# octanis_eps_v03.net
KiCad netlist of a schematic drawn in EAGLE
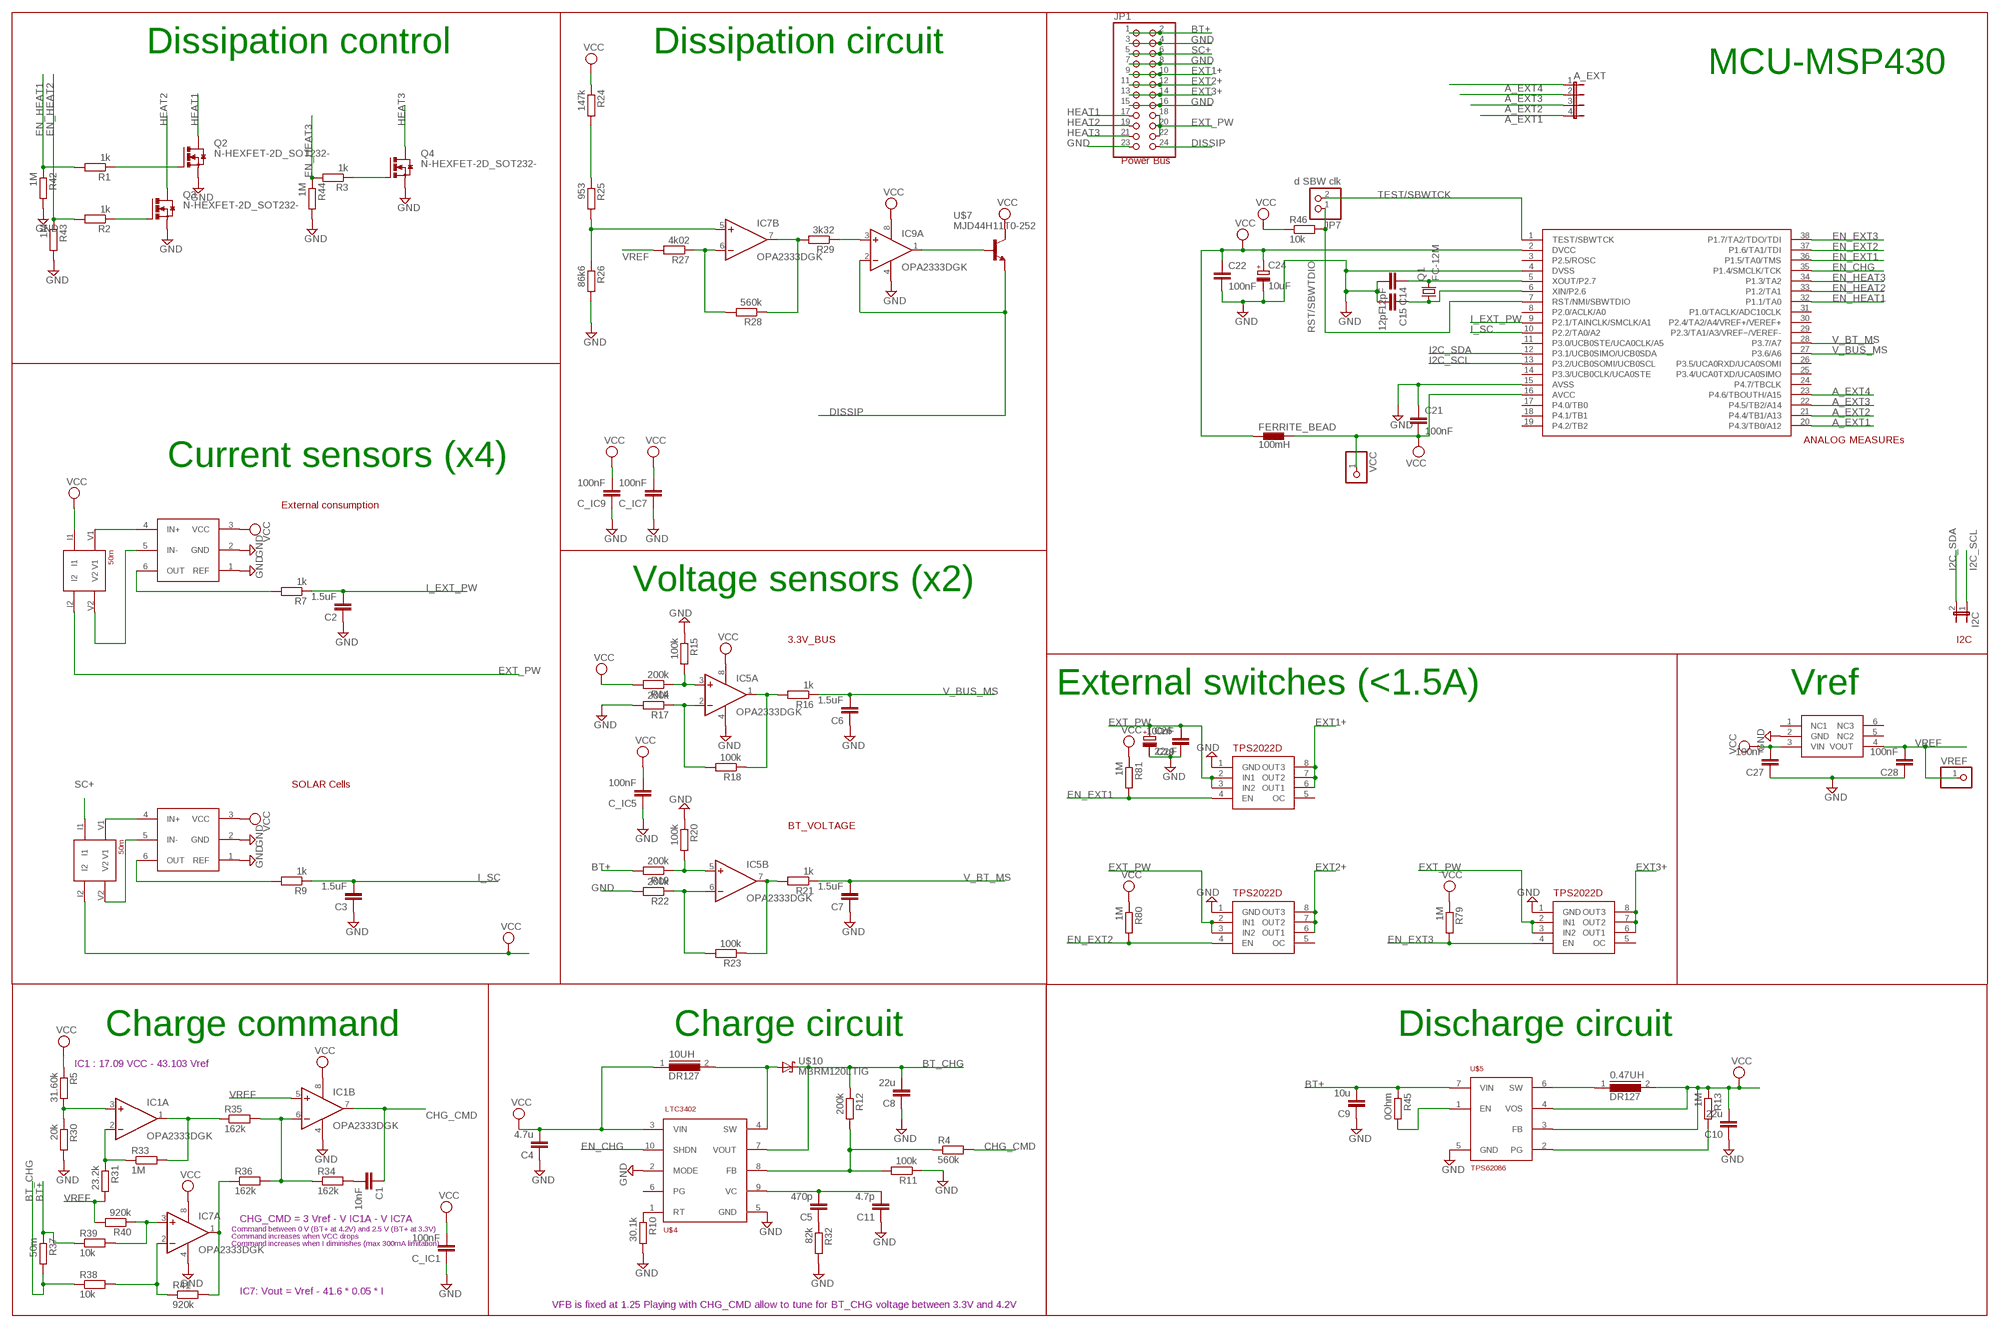
[diagram p0: schematic, sheet 1]

(export (version "E")
  (design (tool "Eeschema 10.0.6"))
  (components
    (comp (ref "0.47UH")
      (value "DR127")
      (footprint "eagle-import:DR127")
      (libsource (lib "eagle-import") (part "DR127"))
    )
    (comp (ref "10UH")
      (value "DR127")
      (footprint "eagle-import:DR127")
      (libsource (lib "eagle-import") (part "DR127"))
    )
    (comp (ref "A_EXT")
      (value "JP4E")
      (footprint "eagle-import:JP4")
      (libsource (lib "eagle-import") (part "JP4E"))
    )
    (comp (ref "C1")
      (value "10nF")
      (footprint "eagle-import:C0603")
      (libsource (lib "eagle-import") (part "C-EUC0603"))
    )
    (comp (ref "C2")
      (value "1.5uF")
      (footprint "eagle-import:C0603")
      (libsource (lib "eagle-import") (part "C-EUC0603"))
    )
    (comp (ref "C3")
      (value "1.5uF")
      (footprint "eagle-import:C0603")
      (libsource (lib "eagle-import") (part "C-EUC0603"))
    )
    (comp (ref "C4")
      (value "4.7u")
      (footprint "eagle-import:C1206")
      (libsource (lib "eagle-import") (part "C-EUC1206"))
    )
    (comp (ref "C5")
      (value "470p")
      (footprint "eagle-import:C0603")
      (libsource (lib "eagle-import") (part "C-EUC0603"))
    )
    (comp (ref "C6")
      (value "1.5uF")
      (footprint "eagle-import:C0603")
      (libsource (lib "eagle-import") (part "C-EUC0603"))
    )
    (comp (ref "C7")
      (value "1.5uF")
      (footprint "eagle-import:C0603")
      (libsource (lib "eagle-import") (part "C-EUC0603"))
    )
    (comp (ref "C8")
      (value "22u")
      (footprint "eagle-import:C0603")
      (libsource (lib "eagle-import") (part "C-EUC0603"))
    )
    (comp (ref "C9")
      (value "10u")
      (footprint "eagle-import:C1206")
      (libsource (lib "eagle-import") (part "C-EUC1206"))
    )
    (comp (ref "C10")
      (value "22u")
      (footprint "eagle-import:C1206")
      (libsource (lib "eagle-import") (part "C-EUC1206"))
    )
    (comp (ref "C11")
      (value "4.7p")
      (footprint "eagle-import:C0603")
      (libsource (lib "eagle-import") (part "C-EUC0603"))
    )
    (comp (ref "C14")
      (value "12pF")
      (footprint "eagle-import:C0603")
      (libsource (lib "eagle-import") (part "C-EUC0603"))
    )
    (comp (ref "C15")
      (value "12pF")
      (footprint "eagle-import:C0603")
      (libsource (lib "eagle-import") (part "C-EUC0603"))
    )
    (comp (ref "C21")
      (value "100nF")
      (footprint "eagle-import:C0603")
      (libsource (lib "eagle-import") (part "C-EUC0603"))
    )
    (comp (ref "C22")
      (value "100nF")
      (footprint "eagle-import:C0603")
      (libsource (lib "eagle-import") (part "C-EUC0603"))
    )
    (comp (ref "C24")
      (value "10uF")
      (footprint "eagle-import:A_3216-18R")
      (libsource (lib "eagle-import") (part "CPOL-EUA/3216-18R"))
    )
    (comp (ref "C26")
      (value "22uF")
      (footprint "eagle-import:A_3216-18R")
      (libsource (lib "eagle-import") (part "CPOL-EUA/3216-18R"))
    )
    (comp (ref "C27")
      (value "100nF")
      (footprint "eagle-import:C0603")
      (libsource (lib "eagle-import") (part "C-EUC0603"))
    )
    (comp (ref "C28")
      (value "100nF")
      (footprint "eagle-import:C0603")
      (libsource (lib "eagle-import") (part "C-EUC0603"))
    )
    (comp (ref "C29")
      (value "100nF")
      (footprint "eagle-import:C0603")
      (libsource (lib "eagle-import") (part "C-EUC0603"))
    )
    (comp (ref "C_IC1")
      (value "100nF")
      (footprint "eagle-import:C0603")
      (libsource (lib "eagle-import") (part "C-EUC0603"))
    )
    (comp (ref "C_IC5")
      (value "100nF")
      (footprint "eagle-import:C0603")
      (libsource (lib "eagle-import") (part "C-EUC0603"))
    )
    (comp (ref "C_IC7")
      (value "100nF")
      (footprint "eagle-import:C0603")
      (libsource (lib "eagle-import") (part "C-EUC0603"))
    )
    (comp (ref "C_IC9")
      (value "100nF")
      (footprint "eagle-import:C0603")
      (libsource (lib "eagle-import") (part "C-EUC0603"))
    )
    (comp (ref "FERRITE_BEAD")
      (value "100mH")
      (footprint "eagle-import:0402")
      (libsource (lib "eagle-import") (part "BLM15HD601SN1"))
    )
    (comp (ref "I2C")
      (value "JP1E")
      (footprint "eagle-import:JP1")
      (libsource (lib "eagle-import") (part "JP1E"))
    )
    (comp (ref "IC1")
      (value "OPA2333DGK")
      (footprint "eagle-import:MSOP08")
      (libsource (lib "eagle-import") (part "OPA2333DGK"))
    )
    (comp (ref "IC5")
      (value "OPA2333DGK")
      (footprint "eagle-import:MSOP08")
      (libsource (lib "eagle-import") (part "OPA2333DGK"))
    )
    (comp (ref "IC7")
      (value "OPA2333DGK")
      (footprint "eagle-import:MSOP08")
      (libsource (lib "eagle-import") (part "OPA2333DGK"))
    )
    (comp (ref "IC9")
      (value "OPA2333DGK")
      (footprint "eagle-import:MSOP08")
      (libsource (lib "eagle-import") (part "OPA2333DGK"))
    )
    (comp (ref "JP1")
      (value "PINHD-2X12")
      (footprint "eagle-import:2X12")
      (libsource (lib "eagle-import") (part "PINHD-2X12"))
    )
    (comp (ref "JP7")
      (value "d SBW clk")
      (footprint "eagle-import:1X02")
      (libsource (lib "eagle-import") (part "PINHD-1X2"))
    )
    (comp (ref "Q1")
      (value "FC-12M")
      (footprint "eagle-import:FC-12M")
      (libsource (lib "eagle-import") (part "FC-12M"))
    )
    (comp (ref "Q2")
      (value "N-HEXFET-2D_SOT232-")
      (footprint "eagle-import:SOT223")
      (libsource (lib "eagle-import") (part "N-HEXFET-2D_?-SOT232"))
    )
    (comp (ref "Q3")
      (value "N-HEXFET-2D_SOT232-")
      (footprint "eagle-import:SOT223")
      (libsource (lib "eagle-import") (part "N-HEXFET-2D_?-SOT232"))
    )
    (comp (ref "Q4")
      (value "N-HEXFET-2D_SOT232-")
      (footprint "eagle-import:SOT223")
      (libsource (lib "eagle-import") (part "N-HEXFET-2D_?-SOT232"))
    )
    (comp (ref "R1")
      (value "1k")
      (footprint "eagle-import:R0603")
      (libsource (lib "eagle-import") (part "R-EU_R0603"))
    )
    (comp (ref "R2")
      (value "1k")
      (footprint "eagle-import:R0603")
      (libsource (lib "eagle-import") (part "R-EU_R0603"))
    )
    (comp (ref "R3")
      (value "1k")
      (footprint "eagle-import:R0603")
      (libsource (lib "eagle-import") (part "R-EU_R0603"))
    )
    (comp (ref "R4")
      (value "560k")
      (footprint "eagle-import:R0603")
      (libsource (lib "eagle-import") (part "R-EU_R0603"))
    )
    (comp (ref "R5")
      (value "31.60k")
      (footprint "eagle-import:R0603")
      (libsource (lib "eagle-import") (part "R-EU_R0603"))
    )
    (comp (ref "R7")
      (value "1k")
      (footprint "eagle-import:R0603")
      (libsource (lib "eagle-import") (part "R-EU_R0603"))
    )
    (comp (ref "R9")
      (value "1k")
      (footprint "eagle-import:R0603")
      (libsource (lib "eagle-import") (part "R-EU_R0603"))
    )
    (comp (ref "R10")
      (value "30.1k")
      (footprint "eagle-import:R0603")
      (libsource (lib "eagle-import") (part "R-EU_R0603"))
    )
    (comp (ref "R11")
      (value "100k")
      (footprint "eagle-import:R0603")
      (libsource (lib "eagle-import") (part "R-EU_R0603"))
    )
    (comp (ref "R12")
      (value "200k")
      (footprint "eagle-import:R0603")
      (libsource (lib "eagle-import") (part "R-EU_R0603"))
    )
    (comp (ref "R13")
      (value "1M")
      (footprint "eagle-import:R0603")
      (libsource (lib "eagle-import") (part "R-EU_R0603"))
    )
    (comp (ref "R14")
      (value "200k")
      (footprint "eagle-import:R0603")
      (libsource (lib "eagle-import") (part "R-EU_R0603"))
    )
    (comp (ref "R15")
      (value "100k")
      (footprint "eagle-import:R0603")
      (libsource (lib "eagle-import") (part "R-EU_R0603"))
    )
    (comp (ref "R16")
      (value "1k")
      (footprint "eagle-import:R0603")
      (libsource (lib "eagle-import") (part "R-EU_R0603"))
    )
    (comp (ref "R17")
      (value "200k")
      (footprint "eagle-import:R0603")
      (libsource (lib "eagle-import") (part "R-EU_R0603"))
    )
    (comp (ref "R18")
      (value "100k")
      (footprint "eagle-import:R0603")
      (libsource (lib "eagle-import") (part "R-EU_R0603"))
    )
    (comp (ref "R19")
      (value "200k")
      (footprint "eagle-import:R0603")
      (libsource (lib "eagle-import") (part "R-EU_R0603"))
    )
    (comp (ref "R20")
      (value "100k")
      (footprint "eagle-import:R0603")
      (libsource (lib "eagle-import") (part "R-EU_R0603"))
    )
    (comp (ref "R21")
      (value "1k")
      (footprint "eagle-import:R0603")
      (libsource (lib "eagle-import") (part "R-EU_R0603"))
    )
    (comp (ref "R22")
      (value "200k")
      (footprint "eagle-import:R0603")
      (libsource (lib "eagle-import") (part "R-EU_R0603"))
    )
    (comp (ref "R23")
      (value "100k")
      (footprint "eagle-import:R0603")
      (libsource (lib "eagle-import") (part "R-EU_R0603"))
    )
    (comp (ref "R24")
      (value "147k")
      (footprint "eagle-import:R0603")
      (libsource (lib "eagle-import") (part "R-EU_R0603"))
    )
    (comp (ref "R25")
      (value "953")
      (footprint "eagle-import:R0603")
      (libsource (lib "eagle-import") (part "R-EU_R0603"))
    )
    (comp (ref "R26")
      (value "86k6")
      (footprint "eagle-import:R0603")
      (libsource (lib "eagle-import") (part "R-EU_R0603"))
    )
    (comp (ref "R27")
      (value "4k02")
      (footprint "eagle-import:R0603")
      (libsource (lib "eagle-import") (part "R-EU_R0603"))
    )
    (comp (ref "R28")
      (value "560k")
      (footprint "eagle-import:R0603")
      (libsource (lib "eagle-import") (part "R-EU_R0603"))
    )
    (comp (ref "R29")
      (value "3k32")
      (footprint "eagle-import:R0603")
      (libsource (lib "eagle-import") (part "R-EU_R0603"))
    )
    (comp (ref "R30")
      (value "20k")
      (footprint "eagle-import:R0603")
      (libsource (lib "eagle-import") (part "R-EU_R0603"))
    )
    (comp (ref "R31")
      (value "23.2k")
      (footprint "eagle-import:R0603")
      (libsource (lib "eagle-import") (part "R-EU_R0603"))
    )
    (comp (ref "R32")
      (value "82k")
      (footprint "eagle-import:R0603")
      (libsource (lib "eagle-import") (part "R-EU_R0603"))
    )
    (comp (ref "R33")
      (value "1M")
      (footprint "eagle-import:R0603")
      (libsource (lib "eagle-import") (part "R-EU_R0603"))
    )
    (comp (ref "R34")
      (value "162k")
      (footprint "eagle-import:R0603")
      (libsource (lib "eagle-import") (part "R-EU_R0603"))
    )
    (comp (ref "R35")
      (value "162k")
      (footprint "eagle-import:R0603")
      (libsource (lib "eagle-import") (part "R-EU_R0603"))
    )
    (comp (ref "R36")
      (value "162k")
      (footprint "eagle-import:R0603")
      (libsource (lib "eagle-import") (part "R-EU_R0603"))
    )
    (comp (ref "R37")
      (value "50m")
      (footprint "eagle-import:R1206")
      (libsource (lib "eagle-import") (part "R-EU_R1206"))
    )
    (comp (ref "R38")
      (value "10k")
      (footprint "eagle-import:R0603")
      (libsource (lib "eagle-import") (part "R-EU_R0603"))
    )
    (comp (ref "R39")
      (value "10k")
      (footprint "eagle-import:R0603")
      (libsource (lib "eagle-import") (part "R-EU_R0603"))
    )
    (comp (ref "R40")
      (value "920k")
      (footprint "eagle-import:R0603")
      (libsource (lib "eagle-import") (part "R-EU_R0603"))
    )
    (comp (ref "R41")
      (value "920k")
      (footprint "eagle-import:R0603")
      (libsource (lib "eagle-import") (part "R-EU_R0603"))
    )
    (comp (ref "R42")
      (value "1M")
      (footprint "eagle-import:R0603")
      (libsource (lib "eagle-import") (part "R-EU_R0603"))
    )
    (comp (ref "R43")
      (value "1M")
      (footprint "eagle-import:R0603")
      (libsource (lib "eagle-import") (part "R-EU_R0603"))
    )
    (comp (ref "R44")
      (value "1M")
      (footprint "eagle-import:R0603")
      (libsource (lib "eagle-import") (part "R-EU_R0603"))
    )
    (comp (ref "R45")
      (value "0Ohm")
      (footprint "eagle-import:R0603")
      (libsource (lib "eagle-import") (part "R-EU_R0603"))
    )
    (comp (ref "R46")
      (value "10k")
      (footprint "eagle-import:R0603")
      (libsource (lib "eagle-import") (part "R-EU_R0603"))
    )
    (comp (ref "R79")
      (value "1M")
      (footprint "eagle-import:R0603")
      (libsource (lib "eagle-import") (part "R-EU_R0603"))
    )
    (comp (ref "R80")
      (value "1M")
      (footprint "eagle-import:R0603")
      (libsource (lib "eagle-import") (part "R-EU_R0603"))
    )
    (comp (ref "R81")
      (value "1M")
      (footprint "eagle-import:R0603")
      (libsource (lib "eagle-import") (part "R-EU_R0603"))
    )
    (comp (ref "U$1")
      (value "50m")
      (footprint "eagle-import:4PADS_RESISTOR")
      (libsource (lib "eagle-import") (part "CURRENT_RESISTOR"))
    )
    (comp (ref "U$2")
      (value "INA213")
      (footprint "eagle-import:SC70-6")
      (libsource (lib "eagle-import") (part "INA213"))
    )
    (comp (ref "U$3")
      (value "INA213")
      (footprint "eagle-import:SC70-6")
      (libsource (lib "eagle-import") (part "INA213"))
    )
    (comp (ref "U$4")
      (value "LTC3402")
      (footprint "eagle-import:MSOP10")
      (libsource (lib "eagle-import") (part "LTC3402"))
    )
    (comp (ref "U$5")
      (value "TPS62086")
      (footprint "eagle-import:QFN-7")
      (libsource (lib "eagle-import") (part "TPS62086"))
    )
    (comp (ref "U$6")
      (value "MSP430G2544")
      (footprint "eagle-import:TSSOP38_MSPGXX44_SERIES")
      (libsource (lib "eagle-import") (part "MSP430G2544"))
    )
    (comp (ref "U$7")
      (value "MJD44H11T0-252")
      (footprint "eagle-import:TO252")
      (libsource (lib "eagle-import") (part "MJD44H11T0-252"))
    )
    (comp (ref "U$8")
      (value "50m")
      (footprint "eagle-import:4PADS_RESISTOR")
      (libsource (lib "eagle-import") (part "CURRENT_RESISTOR"))
    )
    (comp (ref "U$10")
      (value "MBRM120LTIG")
      (footprint "eagle-import:DO216AA")
      (libsource (lib "eagle-import") (part "MBRM120LTIG"))
    )
    (comp (ref "U$16")
      (value "TPS2022D")
      (footprint "eagle-import:SO8")
      (libsource (lib "eagle-import") (part "TPS2022D"))
    )
    (comp (ref "U$17")
      (value "TPS2022D")
      (footprint "eagle-import:SO8")
      (libsource (lib "eagle-import") (part "TPS2022D"))
    )
    (comp (ref "U$18")
      (value "TPS2022D")
      (footprint "eagle-import:SO8")
      (libsource (lib "eagle-import") (part "TPS2022D"))
    )
    (comp (ref "U$19")
      (value "ADR127B")
      (footprint "eagle-import:TSOT23-6")
      (libsource (lib "eagle-import") (part "ADR127B"))
    )
    (comp (ref "VCC")
      (value "PINHD-1X1")
      (footprint "eagle-import:1X01")
      (libsource (lib "eagle-import") (part "PINHD-1X1"))
    )
    (comp (ref "VREF")
      (value "PINHD-1X1")
      (footprint "eagle-import:1X01")
      (libsource (lib "eagle-import") (part "PINHD-1X1"))
    )
  )
  (nets
    (net (code "1") (name "/A_EXT1") (class "Default")
      (node (ref "A_EXT") (pin "4") (pinfunction "4_4") (pintype "passive"))
      (node (ref "U$6") (pin "20") (pinfunction "P4.3/TB0/A12_20") (pintype "bidirectional"))
    )
    (net (code "2") (name "/A_EXT2") (class "Default")
      (node (ref "A_EXT") (pin "3") (pinfunction "3_3") (pintype "passive"))
      (node (ref "U$6") (pin "21") (pinfunction "P4.4/TB1/A13_21") (pintype "bidirectional"))
    )
    (net (code "3") (name "/A_EXT3") (class "Default")
      (node (ref "A_EXT") (pin "2") (pinfunction "2_2") (pintype "passive"))
      (node (ref "U$6") (pin "22") (pinfunction "P4.5/TB2/A14_22") (pintype "bidirectional"))
    )
    (net (code "4") (name "/A_EXT4") (class "Default")
      (node (ref "A_EXT") (pin "1") (pinfunction "1_1") (pintype "passive"))
      (node (ref "U$6") (pin "23") (pinfunction "P4.6/TBOUTH/A15_23") (pintype "bidirectional"))
    )
    (net (code "5") (name "/BT+") (class "Default")
      (node (ref "C9") (pin "2") (pinfunction "2_2") (pintype "passive"))
      (node (ref "JP1") (pin "1") (pinfunction "1_1") (pintype "passive"))
      (node (ref "JP1") (pin "2") (pinfunction "2_2") (pintype "passive"))
      (node (ref "R19") (pin "2") (pinfunction "2_2") (pintype "passive"))
      (node (ref "R37") (pin "1") (pinfunction "1_1") (pintype "passive"))
      (node (ref "R39") (pin "1") (pinfunction "1_1") (pintype "passive"))
      (node (ref "R45") (pin "1") (pinfunction "1_1") (pintype "passive"))
      (node (ref "U$5") (pin "7") (pinfunction "VIN_7") (pintype "bidirectional"))
    )
    (net (code "6") (name "/BT_CHG") (class "Default")
      (node (ref "C8") (pin "2") (pinfunction "2_2") (pintype "passive"))
      (node (ref "R12") (pin "1") (pinfunction "1_1") (pintype "passive"))
      (node (ref "R37") (pin "2") (pinfunction "2_2") (pintype "passive"))
      (node (ref "R38") (pin "1") (pinfunction "1_1") (pintype "passive"))
      (node (ref "U$10") (pin "C") (pinfunction "K_C") (pintype "passive"))
      (node (ref "U$4") (pin "7") (pinfunction "VOUT_7") (pintype "bidirectional"))
    )
    (net (code "7") (name "/CHG_CMD") (class "Default")
      (node (ref "C1") (pin "1") (pinfunction "1_1") (pintype "passive"))
      (node (ref "IC1") (pin "7") (pinfunction "OUT_7") (pintype "output"))
      (node (ref "R4") (pin "2") (pinfunction "2_2") (pintype "passive"))
    )
    (net (code "8") (name "/DISSIP") (class "Default")
      (node (ref "IC9") (pin "2") (pinfunction "-IN_2") (pintype "input"))
      (node (ref "JP1") (pin "24") (pinfunction "24_24") (pintype "passive"))
      (node (ref "U$7") (pin "3") (pinfunction "E_3") (pintype "passive"))
    )
    (net (code "9") (name "/EN_CHG") (class "Default")
      (node (ref "U$4") (pin "10") (pinfunction "SHDN_10") (pintype "bidirectional"))
      (node (ref "U$6") (pin "35") (pinfunction "P1.4/SMCLK/TCK_35") (pintype "bidirectional"))
    )
    (net (code "10") (name "/EN_EXT1") (class "Default")
      (node (ref "R81") (pin "2") (pinfunction "2_2") (pintype "passive"))
      (node (ref "U$16") (pin "4") (pinfunction "EN_4") (pintype "bidirectional"))
      (node (ref "U$6") (pin "36") (pinfunction "P1.5/TA0/TMS_36") (pintype "bidirectional"))
    )
    (net (code "11") (name "/EN_EXT2") (class "Default")
      (node (ref "R80") (pin "2") (pinfunction "2_2") (pintype "passive"))
      (node (ref "U$17") (pin "4") (pinfunction "EN_4") (pintype "bidirectional"))
      (node (ref "U$6") (pin "37") (pinfunction "P1.6/TA1/TDI_37") (pintype "bidirectional"))
    )
    (net (code "12") (name "/EN_EXT3") (class "Default")
      (node (ref "R79") (pin "2") (pinfunction "2_2") (pintype "passive"))
      (node (ref "U$18") (pin "4") (pinfunction "EN_4") (pintype "bidirectional"))
      (node (ref "U$6") (pin "38") (pinfunction "P1.7/TA2/TDO/TDI_38") (pintype "bidirectional"))
    )
    (net (code "13") (name "/EN_HEAT1") (class "Default")
      (node (ref "R1") (pin "2") (pinfunction "2_2") (pintype "passive"))
      (node (ref "R42") (pin "1") (pinfunction "1_1") (pintype "passive"))
      (node (ref "U$6") (pin "32") (pinfunction "P1.1/TA0_32") (pintype "bidirectional"))
    )
    (net (code "14") (name "/EN_HEAT2") (class "Default")
      (node (ref "R2") (pin "2") (pinfunction "2_2") (pintype "passive"))
      (node (ref "R43") (pin "1") (pinfunction "1_1") (pintype "passive"))
      (node (ref "U$6") (pin "33") (pinfunction "P1.2/TA1_33") (pintype "bidirectional"))
    )
    (net (code "15") (name "/EN_HEAT3") (class "Default")
      (node (ref "R3") (pin "2") (pinfunction "2_2") (pintype "passive"))
      (node (ref "R44") (pin "1") (pinfunction "1_1") (pintype "passive"))
      (node (ref "U$6") (pin "34") (pinfunction "P1.3/TA2_34") (pintype "bidirectional"))
    )
    (net (code "16") (name "/EXT1+") (class "Default")
      (node (ref "JP1") (pin "10") (pinfunction "10_10") (pintype "passive"))
      (node (ref "JP1") (pin "9") (pinfunction "9_9") (pintype "passive"))
      (node (ref "U$16") (pin "6") (pinfunction "OUT1_6") (pintype "bidirectional"))
      (node (ref "U$16") (pin "7") (pinfunction "OUT2_7") (pintype "bidirectional"))
      (node (ref "U$16") (pin "8") (pinfunction "OUT3_8") (pintype "bidirectional"))
    )
    (net (code "17") (name "/EXT2+") (class "Default")
      (node (ref "JP1") (pin "11") (pinfunction "11_11") (pintype "passive"))
      (node (ref "JP1") (pin "12") (pinfunction "12_12") (pintype "passive"))
      (node (ref "U$17") (pin "6") (pinfunction "OUT1_6") (pintype "bidirectional"))
      (node (ref "U$17") (pin "7") (pinfunction "OUT2_7") (pintype "bidirectional"))
      (node (ref "U$17") (pin "8") (pinfunction "OUT3_8") (pintype "bidirectional"))
    )
    (net (code "18") (name "/EXT3+") (class "Default")
      (node (ref "JP1") (pin "13") (pinfunction "13_13") (pintype "passive"))
      (node (ref "JP1") (pin "14") (pinfunction "14_14") (pintype "passive"))
      (node (ref "U$18") (pin "6") (pinfunction "OUT1_6") (pintype "bidirectional"))
      (node (ref "U$18") (pin "7") (pinfunction "OUT2_7") (pintype "bidirectional"))
      (node (ref "U$18") (pin "8") (pinfunction "OUT3_8") (pintype "bidirectional"))
    )
    (net (code "19") (name "/EXT_PW") (class "Default")
      (node (ref "C26") (pin "+") (pinfunction "+_+") (pintype "passive"))
      (node (ref "C29") (pin "2") (pinfunction "2_2") (pintype "passive"))
      (node (ref "JP1") (pin "18") (pinfunction "18_18") (pintype "passive"))
      (node (ref "JP1") (pin "20") (pinfunction "20_20") (pintype "passive"))
      (node (ref "JP1") (pin "22") (pinfunction "22_22") (pintype "passive"))
      (node (ref "U$1") (pin "I2") (pinfunction "I2_I2") (pintype "bidirectional"))
      (node (ref "U$16") (pin "2") (pinfunction "IN1_2") (pintype "bidirectional"))
      (node (ref "U$16") (pin "3") (pinfunction "IN2_3") (pintype "bidirectional"))
      (node (ref "U$17") (pin "2") (pinfunction "IN1_2") (pintype "bidirectional"))
      (node (ref "U$17") (pin "3") (pinfunction "IN2_3") (pintype "bidirectional"))
      (node (ref "U$18") (pin "2") (pinfunction "IN1_2") (pintype "bidirectional"))
      (node (ref "U$18") (pin "3") (pinfunction "IN2_3") (pintype "bidirectional"))
    )
    (net (code "20") (name "/HEAT1") (class "Default")
      (node (ref "JP1") (pin "17") (pinfunction "17_17") (pintype "passive"))
      (node (ref "Q2") (pin "2") (pinfunction "D_2") (pintype "passive"))
      (node (ref "Q2") (pin "4") (pinfunction "D_4") (pintype "passive"))
    )
    (net (code "21") (name "/HEAT2") (class "Default")
      (node (ref "JP1") (pin "19") (pinfunction "19_19") (pintype "passive"))
      (node (ref "Q3") (pin "2") (pinfunction "D_2") (pintype "passive"))
      (node (ref "Q3") (pin "4") (pinfunction "D_4") (pintype "passive"))
    )
    (net (code "22") (name "/HEAT3") (class "Default")
      (node (ref "JP1") (pin "21") (pinfunction "21_21") (pintype "passive"))
      (node (ref "Q4") (pin "2") (pinfunction "D_2") (pintype "passive"))
      (node (ref "Q4") (pin "4") (pinfunction "D_4") (pintype "passive"))
    )
    (net (code "23") (name "/I2C_SCL") (class "Default")
      (node (ref "I2C") (pin "1") (pinfunction "1_1") (pintype "passive"))
      (node (ref "U$6") (pin "13") (pinfunction "P3.2/UCB0SOMI/UCB0SCL_13") (pintype "bidirectional"))
    )
    (net (code "24") (name "/I2C_SDA") (class "Default")
      (node (ref "I2C") (pin "2") (pinfunction "2_2") (pintype "passive"))
      (node (ref "U$6") (pin "12") (pinfunction "P3.1/UCB0SIMO/UCB0SDA_12") (pintype "bidirectional"))
    )
    (net (code "25") (name "/I_EXT_PW") (class "Default")
      (node (ref "C2") (pin "2") (pinfunction "2_2") (pintype "passive"))
      (node (ref "R7") (pin "1") (pinfunction "1_1") (pintype "passive"))
      (node (ref "U$6") (pin "9") (pinfunction "P2.1/TAINCLK/SMCLK/A1_9") (pintype "bidirectional"))
    )
    (net (code "26") (name "/I_SC") (class "Default")
      (node (ref "C3") (pin "2") (pinfunction "2_2") (pintype "passive"))
      (node (ref "R9") (pin "1") (pinfunction "1_1") (pintype "passive"))
      (node (ref "U$6") (pin "10") (pinfunction "P2.2/TA0/A2_10") (pintype "bidirectional"))
    )
    (net (code "27") (name "/RST{slash}SBWTDIO") (class "Default")
      (node (ref "JP7") (pin "1") (pinfunction "1_1") (pintype "passive"))
      (node (ref "R46") (pin "2") (pinfunction "2_2") (pintype "passive"))
      (node (ref "U$6") (pin "7") (pinfunction "RST/NMI/SBWTDIO_7") (pintype "bidirectional"))
    )
    (net (code "28") (name "/SC+") (class "Default")
      (node (ref "JP1") (pin "5") (pinfunction "5_5") (pintype "passive"))
      (node (ref "JP1") (pin "6") (pinfunction "6_6") (pintype "passive"))
      (node (ref "U$8") (pin "I1") (pinfunction "I1_I1") (pintype "bidirectional"))
    )
    (net (code "29") (name "/TEST{slash}SBWTCK") (class "Default")
      (node (ref "JP7") (pin "2") (pinfunction "2_2") (pintype "passive"))
      (node (ref "U$6") (pin "1") (pinfunction "TEST/SBWTCK_1") (pintype "bidirectional"))
    )
    (net (code "30") (name "/VREF") (class "Default")
      (node (ref "C28") (pin "2") (pinfunction "2_2") (pintype "passive"))
      (node (ref "IC1") (pin "5") (pinfunction "+IN_5") (pintype "input"))
      (node (ref "R27") (pin "2") (pinfunction "2_2") (pintype "passive"))
      (node (ref "R31") (pin "2") (pinfunction "2_2") (pintype "passive"))
      (node (ref "R40") (pin "2") (pinfunction "2_2") (pintype "passive"))
      (node (ref "U$19") (pin "4") (pinfunction "VOUT_4") (pintype "bidirectional"))
      (node (ref "VREF") (pin "1") (pinfunction "1_1") (pintype "passive"))
    )
    (net (code "31") (name "/V_BT_MS") (class "Default")
      (node (ref "C7") (pin "2") (pinfunction "2_2") (pintype "passive"))
      (node (ref "R21") (pin "1") (pinfunction "1_1") (pintype "passive"))
      (node (ref "U$6") (pin "28") (pinfunction "P3.7/A7_28") (pintype "bidirectional"))
    )
    (net (code "32") (name "/V_BUS_MS") (class "Default")
      (node (ref "C6") (pin "2") (pinfunction "2_2") (pintype "passive"))
      (node (ref "R16") (pin "1") (pinfunction "1_1") (pintype "passive"))
      (node (ref "U$6") (pin "27") (pinfunction "P3.6/A6_27") (pintype "bidirectional"))
    )
    (net (code "33") (name "GND") (class "Default")
      (node (ref "C10") (pin "1") (pinfunction "1_1") (pintype "passive"))
      (node (ref "C11") (pin "1") (pinfunction "1_1") (pintype "passive"))
      (node (ref "C14") (pin "2") (pinfunction "2_2") (pintype "passive"))
      (node (ref "C15") (pin "2") (pinfunction "2_2") (pintype "passive"))
      (node (ref "C2") (pin "1") (pinfunction "1_1") (pintype "passive"))
      (node (ref "C21") (pin "1") (pinfunction "1_1") (pintype "passive"))
      (node (ref "C22") (pin "2") (pinfunction "2_2") (pintype "passive"))
      (node (ref "C24") (pin "-") (pinfunction "-_-") (pintype "passive"))
      (node (ref "C26") (pin "-") (pinfunction "-_-") (pintype "passive"))
      (node (ref "C27") (pin "1") (pinfunction "1_1") (pintype "passive"))
      (node (ref "C28") (pin "1") (pinfunction "1_1") (pintype "passive"))
      (node (ref "C29") (pin "1") (pinfunction "1_1") (pintype "passive"))
      (node (ref "C3") (pin "1") (pinfunction "1_1") (pintype "passive"))
      (node (ref "C4") (pin "1") (pinfunction "1_1") (pintype "passive"))
      (node (ref "C6") (pin "1") (pinfunction "1_1") (pintype "passive"))
      (node (ref "C7") (pin "1") (pinfunction "1_1") (pintype "passive"))
      (node (ref "C8") (pin "1") (pinfunction "1_1") (pintype "passive"))
      (node (ref "C9") (pin "1") (pinfunction "1_1") (pintype "passive"))
      (node (ref "C_IC1") (pin "1") (pinfunction "1_1") (pintype "passive"))
      (node (ref "C_IC5") (pin "1") (pinfunction "1_1") (pintype "passive"))
      (node (ref "C_IC7") (pin "1") (pinfunction "1_1") (pintype "passive"))
      (node (ref "C_IC9") (pin "1") (pinfunction "1_1") (pintype "passive"))
      (node (ref "IC1") (pin "4") (pinfunction "V-_4") (pintype "power_in"))
      (node (ref "IC5") (pin "4") (pinfunction "V-_4") (pintype "power_in"))
      (node (ref "IC7") (pin "4") (pinfunction "V-_4") (pintype "power_in"))
      (node (ref "IC9") (pin "4") (pinfunction "V-_4") (pintype "power_in"))
      (node (ref "JP1") (pin "15") (pinfunction "15_15") (pintype "passive"))
      (node (ref "JP1") (pin "16") (pinfunction "16_16") (pintype "passive"))
      (node (ref "JP1") (pin "23") (pinfunction "23_23") (pintype "passive"))
      (node (ref "JP1") (pin "3") (pinfunction "3_3") (pintype "passive"))
      (node (ref "JP1") (pin "4") (pinfunction "4_4") (pintype "passive"))
      (node (ref "JP1") (pin "7") (pinfunction "7_7") (pintype "passive"))
      (node (ref "JP1") (pin "8") (pinfunction "8_8") (pintype "passive"))
      (node (ref "Q2") (pin "3") (pinfunction "S_3") (pintype "passive"))
      (node (ref "Q3") (pin "3") (pinfunction "S_3") (pintype "passive"))
      (node (ref "Q4") (pin "3") (pinfunction "S_3") (pintype "passive"))
      (node (ref "R10") (pin "2") (pinfunction "2_2") (pintype "passive"))
      (node (ref "R11") (pin "1") (pinfunction "1_1") (pintype "passive"))
      (node (ref "R15") (pin "1") (pinfunction "1_1") (pintype "passive"))
      (node (ref "R17") (pin "2") (pinfunction "2_2") (pintype "passive"))
      (node (ref "R20") (pin "1") (pinfunction "1_1") (pintype "passive"))
      (node (ref "R22") (pin "2") (pinfunction "2_2") (pintype "passive"))
      (node (ref "R26") (pin "2") (pinfunction "2_2") (pintype "passive"))
      (node (ref "R30") (pin "2") (pinfunction "2_2") (pintype "passive"))
      (node (ref "R32") (pin "2") (pinfunction "2_2") (pintype "passive"))
      (node (ref "R42") (pin "2") (pinfunction "2_2") (pintype "passive"))
      (node (ref "R43") (pin "2") (pinfunction "2_2") (pintype "passive"))
      (node (ref "R44") (pin "2") (pinfunction "2_2") (pintype "passive"))
      (node (ref "U$16") (pin "1") (pinfunction "GND_1") (pintype "bidirectional"))
      (node (ref "U$17") (pin "1") (pinfunction "GND_1") (pintype "bidirectional"))
      (node (ref "U$18") (pin "1") (pinfunction "GND_1") (pintype "bidirectional"))
      (node (ref "U$19") (pin "2") (pinfunction "GND_2") (pintype "bidirectional"))
      (node (ref "U$2") (pin "1") (pinfunction "REF_1") (pintype "bidirectional"))
      (node (ref "U$2") (pin "2") (pinfunction "GND_2") (pintype "bidirectional"))
      (node (ref "U$3") (pin "1") (pinfunction "REF_1") (pintype "bidirectional"))
      (node (ref "U$3") (pin "2") (pinfunction "GND_2") (pintype "bidirectional"))
      (node (ref "U$4") (pin "2") (pinfunction "MODE_2") (pintype "bidirectional"))
      (node (ref "U$4") (pin "5") (pinfunction "GND_5") (pintype "bidirectional"))
      (node (ref "U$5") (pin "5") (pinfunction "GND_5") (pintype "bidirectional"))
      (node (ref "U$6") (pin "15") (pinfunction "AVSS_15") (pintype "bidirectional"))
      (node (ref "U$6") (pin "4") (pinfunction "DVSS_4") (pintype "bidirectional"))
    )
    (net (code "34") (name "Net-(C1-Pad2)") (class "Default")
      (node (ref "C1") (pin "2") (pinfunction "2_2") (pintype "passive"))
      (node (ref "R34") (pin "2") (pinfunction "2_2") (pintype "passive"))
    )
    (net (code "35") (name "Net-(C5-Pad1)") (class "Default")
      (node (ref "C5") (pin "1") (pinfunction "1_1") (pintype "passive"))
      (node (ref "R32") (pin "1") (pinfunction "1_1") (pintype "passive"))
    )
    (net (code "36") (name "Net-(IC1A-+IN)") (class "Default")
      (node (ref "IC1") (pin "3") (pinfunction "+IN_3") (pintype "input"))
      (node (ref "R30") (pin "1") (pinfunction "1_1") (pintype "passive"))
      (node (ref "R5") (pin "2") (pinfunction "2_2") (pintype "passive"))
    )
    (net (code "37") (name "Net-(IC1A--IN)") (class "Default")
      (node (ref "IC1") (pin "2") (pinfunction "-IN_2") (pintype "input"))
      (node (ref "R31") (pin "1") (pinfunction "1_1") (pintype "passive"))
      (node (ref "R33") (pin "1") (pinfunction "1_1") (pintype "passive"))
    )
    (net (code "38") (name "Net-(IC1A-OUT)") (class "Default")
      (node (ref "IC1") (pin "1") (pinfunction "OUT_1") (pintype "output"))
      (node (ref "R33") (pin "2") (pinfunction "2_2") (pintype "passive"))
      (node (ref "R35") (pin "1") (pinfunction "1_1") (pintype "passive"))
    )
    (net (code "39") (name "Net-(IC1B--IN)") (class "Default")
      (node (ref "IC1") (pin "6") (pinfunction "-IN_6") (pintype "input"))
      (node (ref "R34") (pin "1") (pinfunction "1_1") (pintype "passive"))
      (node (ref "R35") (pin "2") (pinfunction "2_2") (pintype "passive"))
      (node (ref "R36") (pin "2") (pinfunction "2_2") (pintype "passive"))
    )
    (net (code "40") (name "Net-(IC5A-+IN)") (class "Default")
      (node (ref "IC5") (pin "3") (pinfunction "+IN_3") (pintype "input"))
      (node (ref "R14") (pin "1") (pinfunction "1_1") (pintype "passive"))
      (node (ref "R15") (pin "2") (pinfunction "2_2") (pintype "passive"))
    )
    (net (code "41") (name "Net-(IC5A--IN)") (class "Default")
      (node (ref "IC5") (pin "2") (pinfunction "-IN_2") (pintype "input"))
      (node (ref "R17") (pin "1") (pinfunction "1_1") (pintype "passive"))
      (node (ref "R18") (pin "2") (pinfunction "2_2") (pintype "passive"))
    )
    (net (code "42") (name "Net-(IC5A-OUT)") (class "Default")
      (node (ref "IC5") (pin "1") (pinfunction "OUT_1") (pintype "output"))
      (node (ref "R16") (pin "2") (pinfunction "2_2") (pintype "passive"))
      (node (ref "R18") (pin "1") (pinfunction "1_1") (pintype "passive"))
    )
    (net (code "43") (name "Net-(IC5B-+IN)") (class "Default")
      (node (ref "IC5") (pin "5") (pinfunction "+IN_5") (pintype "input"))
      (node (ref "R19") (pin "1") (pinfunction "1_1") (pintype "passive"))
      (node (ref "R20") (pin "2") (pinfunction "2_2") (pintype "passive"))
    )
    (net (code "44") (name "Net-(IC5B--IN)") (class "Default")
      (node (ref "IC5") (pin "6") (pinfunction "-IN_6") (pintype "input"))
      (node (ref "R22") (pin "1") (pinfunction "1_1") (pintype "passive"))
      (node (ref "R23") (pin "2") (pinfunction "2_2") (pintype "passive"))
    )
    (net (code "45") (name "Net-(IC5B-OUT)") (class "Default")
      (node (ref "IC5") (pin "7") (pinfunction "OUT_7") (pintype "output"))
      (node (ref "R21") (pin "2") (pinfunction "2_2") (pintype "passive"))
      (node (ref "R23") (pin "1") (pinfunction "1_1") (pintype "passive"))
    )
    (net (code "46") (name "Net-(IC7A-+IN)") (class "Default")
      (node (ref "IC7") (pin "3") (pinfunction "+IN_3") (pintype "input"))
      (node (ref "R39") (pin "2") (pinfunction "2_2") (pintype "passive"))
      (node (ref "R40") (pin "1") (pinfunction "1_1") (pintype "passive"))
    )
    (net (code "47") (name "Net-(IC7A--IN)") (class "Default")
      (node (ref "IC7") (pin "2") (pinfunction "-IN_2") (pintype "input"))
      (node (ref "R38") (pin "2") (pinfunction "2_2") (pintype "passive"))
      (node (ref "R41") (pin "1") (pinfunction "1_1") (pintype "passive"))
    )
    (net (code "48") (name "Net-(IC7A-OUT)") (class "Default")
      (node (ref "IC7") (pin "1") (pinfunction "OUT_1") (pintype "output"))
      (node (ref "R36") (pin "1") (pinfunction "1_1") (pintype "passive"))
      (node (ref "R41") (pin "2") (pinfunction "2_2") (pintype "passive"))
    )
    (net (code "49") (name "Net-(IC7B-+IN)") (class "Default")
      (node (ref "IC7") (pin "5") (pinfunction "+IN_5") (pintype "input"))
      (node (ref "R25") (pin "2") (pinfunction "2_2") (pintype "passive"))
      (node (ref "R26") (pin "1") (pinfunction "1_1") (pintype "passive"))
    )
    (net (code "50") (name "Net-(IC7B--IN)") (class "Default")
      (node (ref "IC7") (pin "6") (pinfunction "-IN_6") (pintype "input"))
      (node (ref "R27") (pin "1") (pinfunction "1_1") (pintype "passive"))
      (node (ref "R28") (pin "2") (pinfunction "2_2") (pintype "passive"))
    )
    (net (code "51") (name "Net-(IC7B-OUT)") (class "Default")
      (node (ref "IC7") (pin "7") (pinfunction "OUT_7") (pintype "output"))
      (node (ref "R28") (pin "1") (pinfunction "1_1") (pintype "passive"))
      (node (ref "R29") (pin "2") (pinfunction "2_2") (pintype "passive"))
    )
    (net (code "52") (name "Net-(IC9A-+IN)") (class "Default")
      (node (ref "IC9") (pin "3") (pinfunction "+IN_3") (pintype "input"))
      (node (ref "R29") (pin "1") (pinfunction "1_1") (pintype "passive"))
    )
    (net (code "53") (name "Net-(IC9A-OUT)") (class "Default")
      (node (ref "IC9") (pin "1") (pinfunction "OUT_1") (pintype "output"))
      (node (ref "U$7") (pin "1") (pinfunction "B_1") (pintype "passive"))
    )
    (net (code "54") (name "Net-(Q2-G)") (class "Default")
      (node (ref "Q2") (pin "1") (pinfunction "G_1") (pintype "passive"))
      (node (ref "R1") (pin "1") (pinfunction "1_1") (pintype "passive"))
    )
    (net (code "55") (name "Net-(Q3-G)") (class "Default")
      (node (ref "Q3") (pin "1") (pinfunction "G_1") (pintype "passive"))
      (node (ref "R2") (pin "1") (pinfunction "1_1") (pintype "passive"))
    )
    (net (code "56") (name "Net-(Q4-G)") (class "Default")
      (node (ref "Q4") (pin "1") (pinfunction "G_1") (pintype "passive"))
      (node (ref "R3") (pin "1") (pinfunction "1_1") (pintype "passive"))
    )
    (net (code "57") (name "Net-(R24-Pad2)") (class "Default")
      (node (ref "R24") (pin "2") (pinfunction "2_2") (pintype "passive"))
      (node (ref "R25") (pin "1") (pinfunction "1_1") (pintype "passive"))
    )
    (net (code "58") (name "Net-(U$2-IN+)") (class "Default")
      (node (ref "U$1") (pin "V1") (pinfunction "V1_V1") (pintype "bidirectional"))
      (node (ref "U$2") (pin "4") (pinfunction "IN+_4") (pintype "bidirectional"))
    )
    (net (code "59") (name "Net-(U$2-IN-)") (class "Default")
      (node (ref "U$1") (pin "V2") (pinfunction "V2_V2") (pintype "bidirectional"))
      (node (ref "U$2") (pin "5") (pinfunction "IN-_5") (pintype "bidirectional"))
    )
    (net (code "60") (name "Net-(U$2-OUT)") (class "Default")
      (node (ref "R7") (pin "2") (pinfunction "2_2") (pintype "passive"))
      (node (ref "U$2") (pin "6") (pinfunction "OUT_6") (pintype "bidirectional"))
    )
    (net (code "61") (name "Net-(U$3-IN+)") (class "Default")
      (node (ref "U$3") (pin "4") (pinfunction "IN+_4") (pintype "bidirectional"))
      (node (ref "U$8") (pin "V1") (pinfunction "V1_V1") (pintype "bidirectional"))
    )
    (net (code "62") (name "Net-(U$3-IN-)") (class "Default")
      (node (ref "U$3") (pin "5") (pinfunction "IN-_5") (pintype "bidirectional"))
      (node (ref "U$8") (pin "V2") (pinfunction "V2_V2") (pintype "bidirectional"))
    )
    (net (code "63") (name "Net-(U$3-OUT)") (class "Default")
      (node (ref "R9") (pin "2") (pinfunction "2_2") (pintype "passive"))
      (node (ref "U$3") (pin "6") (pinfunction "OUT_6") (pintype "bidirectional"))
    )
    (net (code "64") (name "Net-(U$4-FB)") (class "Default")
      (node (ref "R11") (pin "2") (pinfunction "2_2") (pintype "passive"))
      (node (ref "R12") (pin "2") (pinfunction "2_2") (pintype "passive"))
      (node (ref "R4") (pin "1") (pinfunction "1_1") (pintype "passive"))
      (node (ref "U$4") (pin "8") (pinfunction "FB_8") (pintype "bidirectional"))
    )
    (net (code "65") (name "Net-(U$4-RT)") (class "Default")
      (node (ref "R10") (pin "1") (pinfunction "1_1") (pintype "passive"))
      (node (ref "U$4") (pin "1") (pinfunction "RT_1") (pintype "bidirectional"))
    )
    (net (code "66") (name "Net-(U$4-SW)") (class "Default")
      (node (ref "10UH") (pin "2") (pinfunction "2_2") (pintype "passive"))
      (node (ref "U$10") (pin "A") (pinfunction "A_A") (pintype "passive"))
      (node (ref "U$4") (pin "4") (pinfunction "SW_4") (pintype "bidirectional"))
    )
    (net (code "67") (name "Net-(U$4-VC)") (class "Default")
      (node (ref "C11") (pin "2") (pinfunction "2_2") (pintype "passive"))
      (node (ref "C5") (pin "2") (pinfunction "2_2") (pintype "passive"))
      (node (ref "U$4") (pin "9") (pinfunction "VC_9") (pintype "bidirectional"))
    )
    (net (code "68") (name "Net-(U$5-EN)") (class "Default")
      (node (ref "R45") (pin "2") (pinfunction "2_2") (pintype "passive"))
      (node (ref "U$5") (pin "1") (pinfunction "EN_1") (pintype "bidirectional"))
    )
    (net (code "69") (name "Net-(U$5-PG)") (class "Default")
      (node (ref "R13") (pin "2") (pinfunction "2_2") (pintype "passive"))
      (node (ref "U$5") (pin "2") (pinfunction "PG_2") (pintype "bidirectional"))
    )
    (net (code "70") (name "Net-(U$5-SW)") (class "Default")
      (node (ref "0.47UH") (pin "1") (pinfunction "1_1") (pintype "passive"))
      (node (ref "U$5") (pin "6") (pinfunction "SW_6") (pintype "bidirectional"))
    )
    (net (code "71") (name "Net-(U$6-XIN{slash}P2.6)") (class "Default")
      (node (ref "C15") (pin "1") (pinfunction "1_1") (pintype "passive"))
      (node (ref "Q1") (pin "1") (pinfunction "1_1") (pintype "passive"))
      (node (ref "U$6") (pin "6") (pinfunction "XIN/P2.6_6") (pintype "bidirectional"))
    )
    (net (code "72") (name "Net-(U$6-XOUT{slash}P2.7)") (class "Default")
      (node (ref "C14") (pin "1") (pinfunction "1_1") (pintype "passive"))
      (node (ref "Q1") (pin "2") (pinfunction "2_2") (pintype "passive"))
      (node (ref "U$6") (pin "5") (pinfunction "XOUT/P2.7_5") (pintype "bidirectional"))
    )
    (net (code "73") (name "VCC") (class "Default")
      (node (ref "0.47UH") (pin "2") (pinfunction "2_2") (pintype "passive"))
      (node (ref "10UH") (pin "1") (pinfunction "1_1") (pintype "passive"))
      (node (ref "C10") (pin "2") (pinfunction "2_2") (pintype "passive"))
      (node (ref "C21") (pin "2") (pinfunction "2_2") (pintype "passive"))
      (node (ref "C22") (pin "1") (pinfunction "1_1") (pintype "passive"))
      (node (ref "C24") (pin "+") (pinfunction "+_+") (pintype "passive"))
      (node (ref "C27") (pin "2") (pinfunction "2_2") (pintype "passive"))
      (node (ref "C4") (pin "2") (pinfunction "2_2") (pintype "passive"))
      (node (ref "C_IC1") (pin "2") (pinfunction "2_2") (pintype "passive"))
      (node (ref "C_IC5") (pin "2") (pinfunction "2_2") (pintype "passive"))
      (node (ref "C_IC7") (pin "2") (pinfunction "2_2") (pintype "passive"))
      (node (ref "C_IC9") (pin "2") (pinfunction "2_2") (pintype "passive"))
      (node (ref "FERRITE_BEAD") (pin "1") (pinfunction "1_1") (pintype "passive"))
      (node (ref "FERRITE_BEAD") (pin "2") (pinfunction "2_2") (pintype "passive"))
      (node (ref "IC1") (pin "8") (pinfunction "V+_8") (pintype "power_in"))
      (node (ref "IC5") (pin "8") (pinfunction "V+_8") (pintype "power_in"))
      (node (ref "IC7") (pin "8") (pinfunction "V+_8") (pintype "power_in"))
      (node (ref "IC9") (pin "8") (pinfunction "V+_8") (pintype "power_in"))
      (node (ref "R13") (pin "1") (pinfunction "1_1") (pintype "passive"))
      (node (ref "R14") (pin "2") (pinfunction "2_2") (pintype "passive"))
      (node (ref "R24") (pin "1") (pinfunction "1_1") (pintype "passive"))
      (node (ref "R46") (pin "1") (pinfunction "1_1") (pintype "passive"))
      (node (ref "R5") (pin "1") (pinfunction "1_1") (pintype "passive"))
      (node (ref "R79") (pin "1") (pinfunction "1_1") (pintype "passive"))
      (node (ref "R80") (pin "1") (pinfunction "1_1") (pintype "passive"))
      (node (ref "R81") (pin "1") (pinfunction "1_1") (pintype "passive"))
      (node (ref "U$1") (pin "I1") (pinfunction "I1_I1") (pintype "bidirectional"))
      (node (ref "U$19") (pin "3") (pinfunction "VIN_3") (pintype "bidirectional"))
      (node (ref "U$2") (pin "3") (pinfunction "VCC_3") (pintype "bidirectional"))
      (node (ref "U$3") (pin "3") (pinfunction "VCC_3") (pintype "bidirectional"))
      (node (ref "U$4") (pin "3") (pinfunction "VIN_3") (pintype "bidirectional"))
      (node (ref "U$5") (pin "3") (pinfunction "FB_3") (pintype "bidirectional"))
      (node (ref "U$5") (pin "4") (pinfunction "VOS_4") (pintype "bidirectional"))
      (node (ref "U$6") (pin "16") (pinfunction "AVCC_16") (pintype "bidirectional"))
      (node (ref "U$6") (pin "2") (pinfunction "DVCC_2") (pintype "bidirectional"))
      (node (ref "U$7") (pin "2") (pinfunction "C_2") (pintype "passive"))
      (node (ref "U$8") (pin "I2") (pinfunction "I2_I2") (pintype "bidirectional"))
      (node (ref "VCC") (pin "1") (pinfunction "1_1") (pintype "passive"))
    )
    (net (code "74") (name "unconnected-(U$4-PG-Pad6)") (class "Default")
      (node (ref "U$4") (pin "6") (pinfunction "PG_6") (pintype "bidirectional"))
    )
    (net (code "75") (name "unconnected-(U$6-P1.0{slash}TACLK{slash}ADC10CLK-Pad31)") (class "Default")
      (node (ref "U$6") (pin "31") (pinfunction "P1.0/TACLK/ADC10CLK_31") (pintype "bidirectional"))
    )
    (net (code "76") (name "unconnected-(U$6-P2.0{slash}ACLK{slash}A0-Pad8)") (class "Default")
      (node (ref "U$6") (pin "8") (pinfunction "P2.0/ACLK/A0_8") (pintype "bidirectional"))
    )
    (net (code "77") (name "unconnected-(U$6-P2.3{slash}TA1{slash}A3{slash}VREF−{slash}VEREF--Pad29)") (class "Default")
      (node (ref "U$6") (pin "29") (pinfunction "P2.3/TA1/A3/VREF−/VEREF-_29") (pintype "bidirectional"))
    )
    (net (code "78") (name "unconnected-(U$6-P2.4{slash}TA2{slash}A4{slash}VREF+{slash}VEREF+-Pad30)") (class "Default")
      (node (ref "U$6") (pin "30") (pinfunction "P2.4/TA2/A4/VREF+/VEREF+_30") (pintype "bidirectional"))
    )
    (net (code "79") (name "unconnected-(U$6-P2.5{slash}ROSC-Pad3)") (class "Default")
      (node (ref "U$6") (pin "3") (pinfunction "P2.5/ROSC_3") (pintype "bidirectional"))
    )
    (net (code "80") (name "unconnected-(U$6-P3.0{slash}UCB0STE{slash}UCA0CLK{slash}A5-Pad11)") (class "Default")
      (node (ref "U$6") (pin "11") (pinfunction "P3.0/UCB0STE/UCA0CLK/A5_11") (pintype "bidirectional"))
    )
    (net (code "81") (name "unconnected-(U$6-P3.3{slash}UCB0CLK{slash}UCA0STE-Pad14)") (class "Default")
      (node (ref "U$6") (pin "14") (pinfunction "P3.3/UCB0CLK/UCA0STE_14") (pintype "bidirectional"))
    )
    (net (code "82") (name "unconnected-(U$6-P3.4{slash}UCA0TXD{slash}UCA0SIMO-Pad25)") (class "Default")
      (node (ref "U$6") (pin "25") (pinfunction "P3.4/UCA0TXD/UCA0SIMO_25") (pintype "bidirectional"))
    )
    (net (code "83") (name "unconnected-(U$6-P3.5{slash}UCA0RXD{slash}UCA0SOMI-Pad26)") (class "Default")
      (node (ref "U$6") (pin "26") (pinfunction "P3.5/UCA0RXD/UCA0SOMI_26") (pintype "bidirectional"))
    )
    (net (code "84") (name "unconnected-(U$6-P4.0{slash}TB0-Pad17)") (class "Default")
      (node (ref "U$6") (pin "17") (pinfunction "P4.0/TB0_17") (pintype "bidirectional"))
    )
    (net (code "85") (name "unconnected-(U$6-P4.1{slash}TB1-Pad18)") (class "Default")
      (node (ref "U$6") (pin "18") (pinfunction "P4.1/TB1_18") (pintype "bidirectional"))
    )
    (net (code "86") (name "unconnected-(U$6-P4.2{slash}TB2-Pad19)") (class "Default")
      (node (ref "U$6") (pin "19") (pinfunction "P4.2/TB2_19") (pintype "bidirectional"))
    )
    (net (code "87") (name "unconnected-(U$6-P4.7{slash}TBCLK-Pad24)") (class "Default")
      (node (ref "U$6") (pin "24") (pinfunction "P4.7/TBCLK_24") (pintype "bidirectional"))
    )
    (net (code "88") (name "unconnected-(U$16-OC-Pad5)") (class "Default")
      (node (ref "U$16") (pin "5") (pinfunction "OC_5") (pintype "bidirectional"))
    )
    (net (code "89") (name "unconnected-(U$17-OC-Pad5)") (class "Default")
      (node (ref "U$17") (pin "5") (pinfunction "OC_5") (pintype "bidirectional"))
    )
    (net (code "90") (name "unconnected-(U$18-OC-Pad5)") (class "Default")
      (node (ref "U$18") (pin "5") (pinfunction "OC_5") (pintype "bidirectional"))
    )
    (net (code "91") (name "unconnected-(U$19-NC1-Pad1)") (class "Default")
      (node (ref "U$19") (pin "1") (pinfunction "NC1_1") (pintype "bidirectional"))
    )
    (net (code "92") (name "unconnected-(U$19-NC2-Pad5)") (class "Default")
      (node (ref "U$19") (pin "5") (pinfunction "NC2_5") (pintype "bidirectional"))
    )
    (net (code "93") (name "unconnected-(U$19-NC3-Pad6)") (class "Default")
      (node (ref "U$19") (pin "6") (pinfunction "NC3_6") (pintype "bidirectional"))
    )
  )
)
